# River_Level_Sensor_Datalogger.net
KiCad netlist of a schematic drawn in Altium Designer
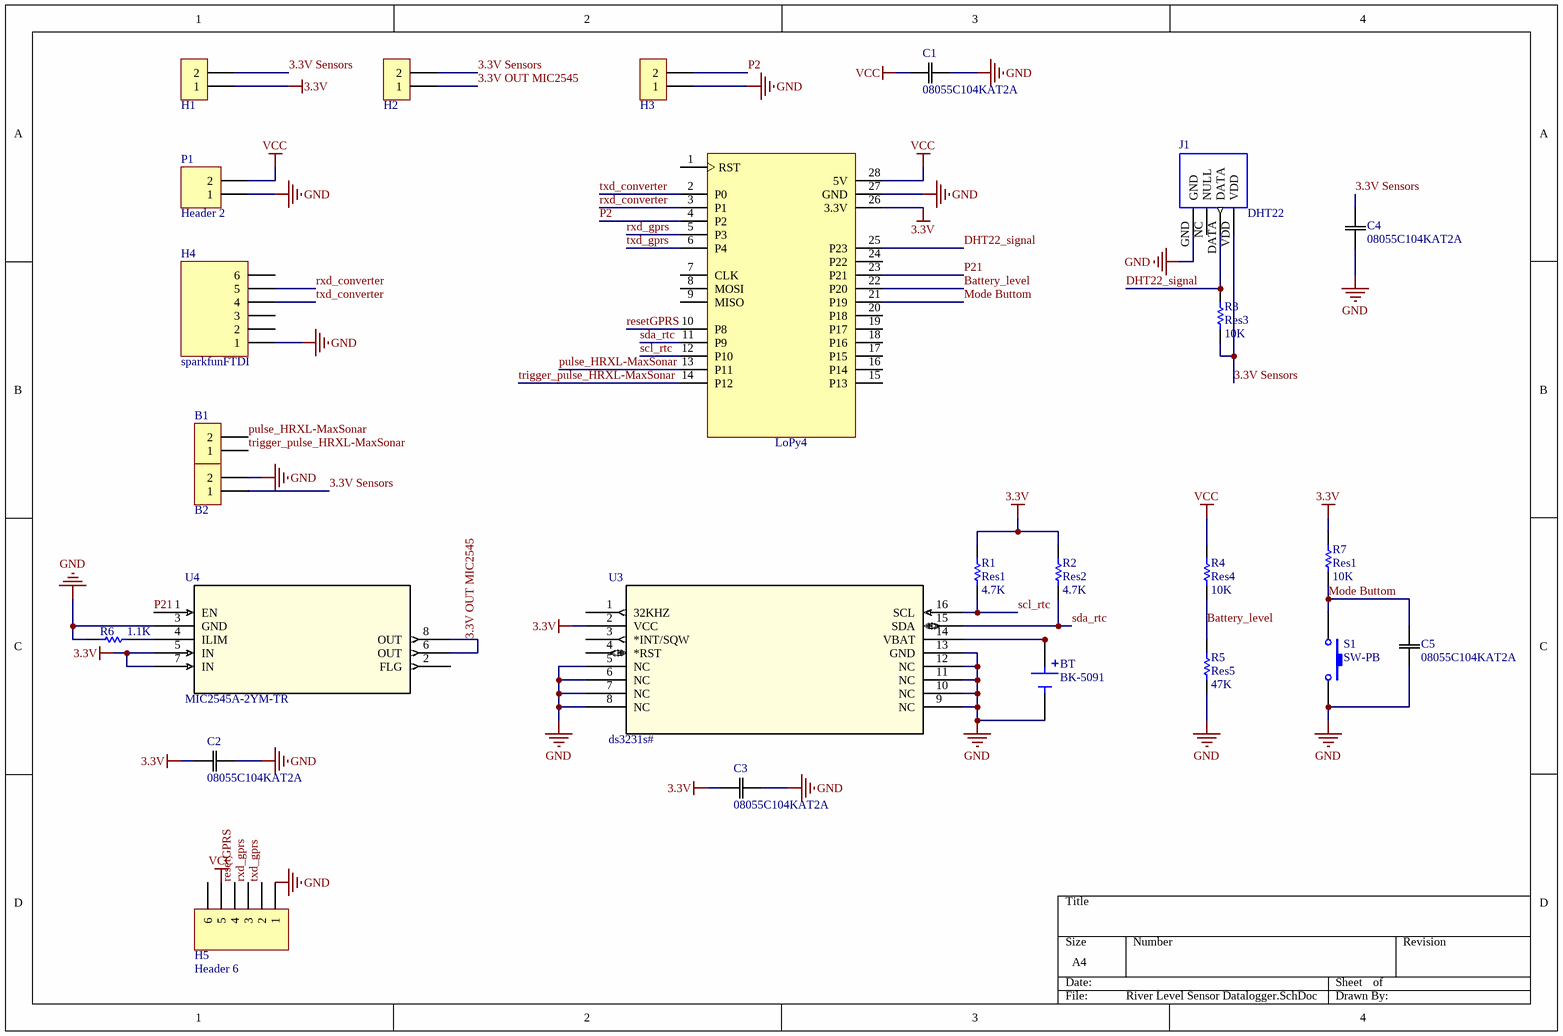
[diagram p0: River Level Sensor Datalogger.SchDoc]

(export (version "E")
  (design (tool "Eeschema 10.0.6"))
  (components
    (comp (ref "B1")
      (value "Borne")
      (footprint "BORNE2")
      (description "Terminal Atornillable 2 salidas")
      (libsource (lib "Conectores") (part "Borne2"))
    )
    (comp (ref "B2")
      (value "Borne")
      (footprint "BORNE2")
      (description "Terminal Atornillable 2 salidas")
      (libsource (lib "Conectores") (part "Borne2"))
    )
    (comp (ref "BT")
      (value "BK-5091")
      (footprint "SnapEDApcb:BAT_BK-5091")
      (description "Battery Retainer Coin, 11.6mm 1 Cell PC Pin")
      (fields (field (name "MF") "MPD") (field (name "DIGI-KEY_PART_NUMBER") "BK-5091-ND"))
      (libsource (lib "SnapEDAsch") (part "BK-5091"))
    )
    (comp (ref "C1")
      (value "08055C104KAT2A")
      (footprint "CAP_X7R_0805_AVX")
      (description "No Description Available")
      (fields (field (name "COPYRIGHT") "Copyright (C) 2018 Accelerated Designs. All rights reserved"))
      (libsource (lib "cap_0805") (part "08055C104KAT2A"))
    )
    (comp (ref "C2")
      (value "08055C104KAT2A")
      (footprint "CAP_X7R_0805_AVX")
      (description "No Description Available")
      (fields (field (name "COPYRIGHT") "Copyright (C) 2018 Accelerated Designs. All rights reserved"))
      (libsource (lib "cap_0805") (part "08055C104KAT2A"))
    )
    (comp (ref "C3")
      (value "08055C104KAT2A")
      (footprint "CAP_X7R_0805_AVX")
      (description "No Description Available")
      (fields (field (name "COPYRIGHT") "Copyright (C) 2018 Accelerated Designs. All rights reserved"))
      (libsource (lib "cap_0805") (part "08055C104KAT2A"))
    )
    (comp (ref "C4")
      (value "08055C104KAT2A")
      (footprint "CAP_X7R_0805_AVX")
      (description "No Description Available")
      (fields (field (name "COPYRIGHT") "Copyright (C) 2018 Accelerated Designs. All rights reserved"))
      (libsource (lib "cap_0805") (part "08055C104KAT2A"))
    )
    (comp (ref "C5")
      (value "08055C104KAT2A")
      (footprint "CAP_X7R_0805_AVX")
      (description "No Description Available")
      (fields (field (name "COPYRIGHT") "Copyright (C) 2018 Accelerated Designs. All rights reserved"))
      (libsource (lib "cap_0805") (part "08055C104KAT2A"))
    )
    (comp (ref "H1")
      (value "Header")
      (footprint "Header 1X2")
      (description "Header 2 pin")
      (libsource (lib "Conectores") (part "Header 2"))
    )
    (comp (ref "H2")
      (value "Header")
      (footprint "Header 1X2")
      (description "Header 2 pin")
      (libsource (lib "Conectores") (part "Header 2"))
    )
    (comp (ref "H3")
      (value "Header")
      (footprint "Header 1X2")
      (description "Header 2 pin")
      (libsource (lib "Conectores") (part "Header 2"))
    )
    (comp (ref "H4")
      (value "sparkfunFTDI")
      (footprint "sparkfunFTDI")
      (description "Header, 6-Pin")
      (fields (field (name "PUBLISHER") "Altium Limited"))
      (libsource (lib "Conectores") (part "sparkfunFTDI"))
    )
    (comp (ref "H5")
      (value "Header 6")
      (footprint "Header 1X6")
      (description "Header, 6-Pin")
      (fields (field (name "PUBLISHER") "Altium Limited"))
      (libsource (lib "Conectores") (part "Header 6"))
    )
    (comp (ref "J1")
      (value "DHT22")
      (footprint "DHT22:DHT22")
      (description "Capacitive-type humidity and temperature module/sensor")
      (fields (field (name "MF") "Aosong Electronics"))
      (libsource (lib "DHT22") (part "DHT22"))
    )
    (comp (ref "P1")
      (value "Header 2")
      (footprint "BORNERA25-2")
      (description "Header, 2-Pin")
      (fields (field (name "PUBLISHER") "Altium Limited"))
      (libsource (lib "Miscellaneous Connectors_3D") (part "Header 2"))
    )
    (comp (ref "R1")
      (value "Res1")
      (footprint "0805")
      (description "Resistor")
      (fields (field (name "ALTIUM_VALUE") "4.7K") (field (name "PUBLISHER") "Altium Limited"))
      (libsource (lib "Miscellaneous Devices") (part "Res1"))
    )
    (comp (ref "R2")
      (value "Res2")
      (footprint "0805")
      (description "Resistor")
      (fields (field (name "ALTIUM_VALUE") "4.7K") (field (name "PUBLISHER") "Altium Limited"))
      (libsource (lib "Miscellaneous Devices") (part "Res1"))
    )
    (comp (ref "R3")
      (value "Res3")
      (footprint "0805")
      (description "Resistor")
      (fields (field (name "ALTIUM_VALUE") "10K") (field (name "PUBLISHER") "Altium Limited"))
      (libsource (lib "Miscellaneous Devices") (part "Res1"))
    )
    (comp (ref "R4")
      (value "Res4")
      (footprint "0805")
      (description "Resistor")
      (fields (field (name "ALTIUM_VALUE") "10K") (field (name "PUBLISHER") "Altium Limited"))
      (libsource (lib "Miscellaneous Devices") (part "Res1"))
    )
    (comp (ref "R5")
      (value "Res5")
      (footprint "0805")
      (description "Resistor")
      (fields (field (name "ALTIUM_VALUE") "47K") (field (name "PUBLISHER") "Altium Limited"))
      (libsource (lib "Miscellaneous Devices") (part "Res1"))
    )
    (comp (ref "R6")
      (value "1.1K")
      (footprint "0805")
      (description "Resistor")
      (fields (field (name "PUBLISHER") "Altium Limited"))
      (libsource (lib "Miscellaneous Devices") (part "Res1"))
    )
    (comp (ref "R7")
      (value "Res1")
      (footprint "0805")
      (description "Resistor")
      (fields (field (name "ALTIUM_VALUE") "10K") (field (name "PUBLISHER") "Altium Limited"))
      (libsource (lib "Miscellaneous Devices") (part "Res1"))
    )
    (comp (ref "S1")
      (value "SW-PB")
      (footprint "BUTTON-1-SMD")
      (description "Switch")
      (fields (field (name "PUBLISHER") "Altium Limited"))
      (libsource (lib "Miscellaneous Devices") (part "SW-PB"))
    )
    (comp (ref "U2")
      (value "LoPy4")
      (footprint "LoPy")
      (fields (field (name "PUBLISHER") "Altium Limited"))
      (libsource (lib "LoPy") (part "LoPy"))
    )
    (comp (ref "U3")
      (value "ds3231s#")
      (footprint "21-0042B_16_MXM")
      (description "No Description Available")
      (fields (field (name "COPYRIGHT") "Copyright (C) 2018 Accelerated Designs. All rights reserved"))
      (libsource (lib "2021-01-26_16-05-58") (part "ds3231s#"))
    )
    (comp (ref "U4")
      (value "MIC2545A-2YM-TR")
      (footprint "SOP-8_MCH")
      (description "No Description Available")
      (fields (field (name "COPYRIGHT") "Copyright (C) 2018 Accelerated Designs. All rights reserved"))
      (libsource (lib "MIC2545A-2YM-TR") (part "MIC2545A-2YM-TR"))
    )
  )
  (nets
    (net (code "1") (name "/3.3V OUT MIC2545") (class "Default")
      (node (ref "H2") (pin "1") (pinfunction "1_1") (pintype "passive"))
      (node (ref "U4") (pin "6") (pinfunction "OUT_6") (pintype "output"))
      (node (ref "U4") (pin "8") (pinfunction "OUT_8") (pintype "output"))
    )
    (net (code "2") (name "/3.3V Sensors") (class "Default")
      (node (ref "B2") (pin "1") (pinfunction "1_1") (pintype "passive"))
      (node (ref "C4") (pin "2") (pinfunction "2_2") (pintype "passive"))
      (node (ref "H1") (pin "2") (pinfunction "2_2") (pintype "passive"))
      (node (ref "H2") (pin "2") (pinfunction "2_2") (pintype "passive"))
      (node (ref "J1") (pin "VDD") (pinfunction "VDD_VDD") (pintype "power_in"))
      (node (ref "R3") (pin "2") (pinfunction "2_2") (pintype "passive"))
    )
    (net (code "3") (name "/Battery_level") (class "Default")
      (node (ref "R4") (pin "2") (pinfunction "2_2") (pintype "passive"))
      (node (ref "R5") (pin "1") (pinfunction "1_1") (pintype "passive"))
      (node (ref "U2") (pin "22") (pinfunction "P20_22") (pintype "passive"))
    )
    (net (code "4") (name "/DHT22_signal") (class "Default")
      (node (ref "J1") (pin "DATA") (pinfunction "DATA_DATA") (pintype "output"))
      (node (ref "R3") (pin "1") (pinfunction "1_1") (pintype "passive"))
      (node (ref "U2") (pin "25") (pinfunction "P23_25") (pintype "passive"))
    )
    (net (code "5") (name "/Mode Buttom") (class "Default")
      (node (ref "C5") (pin "2") (pinfunction "2_2") (pintype "passive"))
      (node (ref "R7") (pin "2") (pinfunction "2_2") (pintype "passive"))
      (node (ref "S1") (pin "1") (pinfunction "1_1") (pintype "passive"))
      (node (ref "U2") (pin "21") (pinfunction "P19_21") (pintype "passive"))
    )
    (net (code "6") (name "/P2") (class "Default")
      (node (ref "H3") (pin "2") (pinfunction "2_2") (pintype "passive"))
      (node (ref "U2") (pin "4") (pinfunction "P2_4") (pintype "passive"))
    )
    (net (code "7") (name "/P21") (class "Default")
      (node (ref "U2") (pin "23") (pinfunction "P21_23") (pintype "passive"))
      (node (ref "U4") (pin "1") (pinfunction "EN_1") (pintype "input"))
    )
    (net (code "8") (name "/pulse_HRXL-MaxSonar") (class "Default")
      (node (ref "B1") (pin "2") (pinfunction "2_2") (pintype "passive"))
      (node (ref "U2") (pin "13") (pinfunction "P11_13") (pintype "passive"))
    )
    (net (code "9") (name "/resetGPRS") (class "Default")
      (node (ref "H5") (pin "4") (pinfunction "4_4") (pintype "passive"))
      (node (ref "U2") (pin "10") (pinfunction "P8_10") (pintype "passive"))
    )
    (net (code "10") (name "/rxd_converter") (class "Default")
      (node (ref "H4") (pin "5") (pinfunction "5_5") (pintype "passive"))
      (node (ref "U2") (pin "3") (pinfunction "P1_3") (pintype "passive"))
    )
    (net (code "11") (name "/rxd_gprs") (class "Default")
      (node (ref "H5") (pin "3") (pinfunction "3_3") (pintype "passive"))
      (node (ref "U2") (pin "5") (pinfunction "P3_5") (pintype "passive"))
    )
    (net (code "12") (name "/scl_rtc") (class "Default")
      (node (ref "R1") (pin "2") (pinfunction "2_2") (pintype "passive"))
      (node (ref "U2") (pin "12") (pinfunction "P10_12") (pintype "passive"))
      (node (ref "U3") (pin "16") (pinfunction "SCL_16") (pintype "input"))
    )
    (net (code "13") (name "/sda_rtc") (class "Default")
      (node (ref "R2") (pin "2") (pinfunction "2_2") (pintype "passive"))
      (node (ref "U2") (pin "11") (pinfunction "P9_11") (pintype "passive"))
      (node (ref "U3") (pin "15") (pinfunction "SDA_15") (pintype "bidirectional"))
    )
    (net (code "14") (name "/trigger_pulse_HRXL-MaxSonar") (class "Default")
      (node (ref "B1") (pin "1") (pinfunction "1_1") (pintype "passive"))
      (node (ref "U2") (pin "14") (pinfunction "P12_14") (pintype "passive"))
    )
    (net (code "15") (name "/txd_converter") (class "Default")
      (node (ref "H4") (pin "4") (pinfunction "4_4") (pintype "passive"))
      (node (ref "U2") (pin "2") (pinfunction "P0_2") (pintype "power_in"))
    )
    (net (code "16") (name "/txd_gprs") (class "Default")
      (node (ref "H5") (pin "2") (pinfunction "2_2") (pintype "passive"))
      (node (ref "U2") (pin "6") (pinfunction "P4_6") (pintype "passive"))
    )
    (net (code "17") (name "3.3V") (class "Default")
      (node (ref "C2") (pin "2") (pinfunction "2_2") (pintype "passive"))
      (node (ref "C3") (pin "2") (pinfunction "2_2") (pintype "passive"))
      (node (ref "H1") (pin "1") (pinfunction "1_1") (pintype "passive"))
      (node (ref "R1") (pin "1") (pinfunction "1_1") (pintype "passive"))
      (node (ref "R2") (pin "1") (pinfunction "1_1") (pintype "passive"))
      (node (ref "R7") (pin "1") (pinfunction "1_1") (pintype "passive"))
      (node (ref "U2") (pin "26") (pinfunction "3.3V_26") (pintype "passive"))
      (node (ref "U3") (pin "2") (pinfunction "VCC_2") (pintype "power_in"))
      (node (ref "U4") (pin "5") (pinfunction "IN_5") (pintype "input"))
      (node (ref "U4") (pin "7") (pinfunction "IN_7") (pintype "input"))
    )
    (net (code "18") (name "GND") (class "Default")
      (node (ref "B2") (pin "2") (pinfunction "2_2") (pintype "passive"))
      (node (ref "BT") (pin "NEG") (pinfunction "NEG_NEG") (pintype "passive"))
      (node (ref "C1") (pin "1") (pinfunction "1_1") (pintype "passive"))
      (node (ref "C2") (pin "1") (pinfunction "1_1") (pintype "passive"))
      (node (ref "C3") (pin "1") (pinfunction "1_1") (pintype "passive"))
      (node (ref "C4") (pin "1") (pinfunction "1_1") (pintype "passive"))
      (node (ref "C5") (pin "1") (pinfunction "1_1") (pintype "passive"))
      (node (ref "H3") (pin "1") (pinfunction "1_1") (pintype "passive"))
      (node (ref "H4") (pin "1") (pinfunction "1_1") (pintype "passive"))
      (node (ref "H5") (pin "1") (pinfunction "1_1") (pintype "passive"))
      (node (ref "J1") (pin "GND") (pinfunction "GND_GND") (pintype "power_in"))
      (node (ref "P1") (pin "1") (pinfunction "1_1") (pintype "passive"))
      (node (ref "R5") (pin "2") (pinfunction "2_2") (pintype "passive"))
      (node (ref "R6") (pin "1") (pinfunction "1_1") (pintype "passive"))
      (node (ref "S1") (pin "2") (pinfunction "2_2") (pintype "passive"))
      (node (ref "U2") (pin "27") (pinfunction "GND_27") (pintype "passive"))
      (node (ref "U3") (pin "10") (pinfunction "NC_10") (pintype "passive"))
      (node (ref "U3") (pin "11") (pinfunction "NC_11") (pintype "passive"))
      (node (ref "U3") (pin "12") (pinfunction "NC_12") (pintype "passive"))
      (node (ref "U3") (pin "13") (pinfunction "GND_13") (pintype "power_in"))
      (node (ref "U3") (pin "5") (pinfunction "NC_5") (pintype "passive"))
      (node (ref "U3") (pin "6") (pinfunction "NC_6") (pintype "passive"))
      (node (ref "U3") (pin "7") (pinfunction "NC_7") (pintype "passive"))
      (node (ref "U3") (pin "8") (pinfunction "NC_8") (pintype "passive"))
      (node (ref "U3") (pin "9") (pinfunction "NC_9") (pintype "passive"))
      (node (ref "U4") (pin "3") (pinfunction "GND_3") (pintype "power_in"))
    )
    (net (code "19") (name "Net-(U3-VBAT)") (class "Default")
      (node (ref "BT") (pin "1+") (pinfunction "POS_1+") (pintype "passive"))
      (node (ref "BT") (pin "2+") (pinfunction "POS_2+") (pintype "passive"))
      (node (ref "U3") (pin "14") (pinfunction "VBAT_14") (pintype "power_in"))
    )
    (net (code "20") (name "Net-(U4-ILIM)") (class "Default")
      (node (ref "R6") (pin "2") (pinfunction "2_2") (pintype "passive"))
      (node (ref "U4") (pin "4") (pinfunction "ILIM_4") (pintype "passive"))
    )
    (net (code "21") (name "VCC") (class "Default")
      (node (ref "C1") (pin "2") (pinfunction "2_2") (pintype "passive"))
      (node (ref "H5") (pin "5") (pinfunction "5_5") (pintype "passive"))
      (node (ref "P1") (pin "2") (pinfunction "2_2") (pintype "passive"))
      (node (ref "R4") (pin "1") (pinfunction "1_1") (pintype "passive"))
      (node (ref "U2") (pin "28") (pinfunction "5V_28") (pintype "passive"))
    )
    (net (code "22") (name "unconnected-(H4-Pad2)") (class "Default")
      (node (ref "H4") (pin "2") (pinfunction "2_2") (pintype "passive"))
    )
    (net (code "23") (name "unconnected-(H4-Pad3)") (class "Default")
      (node (ref "H4") (pin "3") (pinfunction "3_3") (pintype "passive"))
    )
    (net (code "24") (name "unconnected-(H4-Pad6)") (class "Default")
      (node (ref "H4") (pin "6") (pinfunction "6_6") (pintype "passive"))
    )
    (net (code "25") (name "unconnected-(H5-Pad6)") (class "Default")
      (node (ref "H5") (pin "6") (pinfunction "6_6") (pintype "passive"))
    )
    (net (code "26") (name "unconnected-(J1-NULL-PadNC)") (class "Default")
      (node (ref "J1") (pin "NC") (pinfunction "NULL_NC") (pintype "passive"))
    )
    (net (code "27") (name "unconnected-(U2-CLK-Pad7)") (class "Default")
      (node (ref "U2") (pin "7") (pinfunction "CLK_7") (pintype "passive"))
    )
    (net (code "28") (name "unconnected-(U2-MISO-Pad9)") (class "Default")
      (node (ref "U2") (pin "9") (pinfunction "MISO_9") (pintype "passive"))
    )
    (net (code "29") (name "unconnected-(U2-MOSI-Pad8)") (class "Default")
      (node (ref "U2") (pin "8") (pinfunction "MOSI_8") (pintype "passive"))
    )
    (net (code "30") (name "unconnected-(U2-P13-Pad15)") (class "Default")
      (node (ref "U2") (pin "15") (pinfunction "P13_15") (pintype "passive"))
    )
    (net (code "31") (name "unconnected-(U2-P14-Pad16)") (class "Default")
      (node (ref "U2") (pin "16") (pinfunction "P14_16") (pintype "passive"))
    )
    (net (code "32") (name "unconnected-(U2-P15-Pad17)") (class "Default")
      (node (ref "U2") (pin "17") (pinfunction "P15_17") (pintype "passive"))
    )
    (net (code "33") (name "unconnected-(U2-P16-Pad18)") (class "Default")
      (node (ref "U2") (pin "18") (pinfunction "P16_18") (pintype "passive"))
    )
    (net (code "34") (name "unconnected-(U2-P17-Pad19)") (class "Default")
      (node (ref "U2") (pin "19") (pinfunction "P17_19") (pintype "passive"))
    )
    (net (code "35") (name "unconnected-(U2-P18-Pad20)") (class "Default")
      (node (ref "U2") (pin "20") (pinfunction "P18_20") (pintype "passive"))
    )
    (net (code "36") (name "unconnected-(U2-P22-Pad24)") (class "Default")
      (node (ref "U2") (pin "24") (pinfunction "P22_24") (pintype "passive"))
    )
    (net (code "37") (name "unconnected-(U2-RST-Pad1)") (class "Default")
      (node (ref "U2") (pin "1") (pinfunction "RST_1") (pintype "passive"))
    )
    (net (code "38") (name "unconnected-(U3-*INT{slash}SQW-Pad3)") (class "Default")
      (node (ref "U3") (pin "3") (pinfunction "*INT/SQW_3") (pintype "output"))
    )
    (net (code "39") (name "unconnected-(U3-*RST-Pad4)") (class "Default")
      (node (ref "U3") (pin "4") (pinfunction "*RST_4") (pintype "bidirectional"))
    )
    (net (code "40") (name "unconnected-(U3-32KHZ-Pad1)") (class "Default")
      (node (ref "U3") (pin "1") (pinfunction "32KHZ_1") (pintype "output"))
    )
    (net (code "41") (name "unconnected-(U4-FLG-Pad2)") (class "Default")
      (node (ref "U4") (pin "2") (pinfunction "FLG_2") (pintype "output"))
    )
  )
)
